# Power.net
KiCad netlist of a schematic drawn in Altium Designer
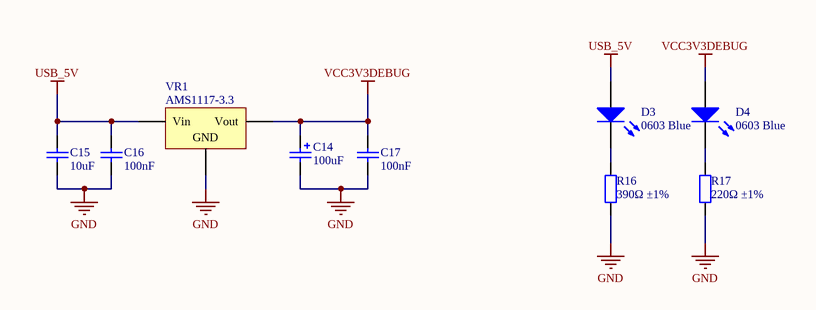
[diagram p0: Power.SchDoc]

(export (version "E")
  (design (tool "Eeschema 10.0.6"))
  (components
    (comp (ref "C14")
      (value "100uF")
      (footprint "CASE-B_3528")
      (description "Tantalum capacitor")
      (fields (field (name "MANUFACTURER") "AVX") (field (name "PARTNUMBER") "TAJB107K006RNJ"))
      (libsource (lib "Cap") (part "3528 100uF (107) 10% 6.3V"))
    )
    (comp (ref "C15")
      (value "10uF")
      (footprint "1206_C")
      (description "Chip capacitors")
      (fields
        (field (name "MANUFACTURER") "Samsung Electro-Mechanics")
        (field (name "PARTNUMBER") "CL31A106KBHNNNE")
      )
      (libsource (lib "Cap") (part "1206 10uF (106) 10% 50V"))
    )
    (comp (ref "C16")
      (value "100nF")
      (footprint "0402_C")
      (description "Chip capacitors")
      (fields
        (field (name "MANUFACTURER") "Samsung Electro-Mechanics")
        (field (name "PARTNUMBER") "CL05B104KO5NNNC")
      )
      (libsource (lib "Miscellaneous Devices LC") (part "0402 100nF (104) 10% 16V"))
    )
    (comp (ref "C17")
      (value "100nF")
      (footprint "1206_C")
      (description "Chip capacitors")
      (fields
        (field (name "MANUFACTURER") "Samsung Electro-Mechanics")
        (field (name "PARTNUMBER") "CL31B104KBCNNNC")
      )
      (libsource (lib "Miscellaneous Devices LC") (part "1206 100nF (104) 10% 50V"))
    )
    (comp (ref "D3")
      (value "0603 Blue")
      (footprint "0603_LED_S1")
      (description "LED")
      (libsource (lib "Miscellaneous Devices LC") (part "0603 LED Blue"))
    )
    (comp (ref "D4")
      (value "0603 Blue")
      (footprint "0603_LED_S1")
      (description "LED")
      (libsource (lib "Miscellaneous Devices LC") (part "0603 LED Blue"))
    )
    (comp (ref "R16")
      (value "390Ω ±1%")
      (footprint "0603_R")
      (description "Chip resistor")
      (fields (field (name "MANUFACTURER") "Uniroyal Elec") (field (name "PARTNUMBER") "0603WAF3900T5E"))
      (libsource (lib "RES") (part "0603 390R (3900) 1%"))
    )
    (comp (ref "R17")
      (value "220Ω ±1%")
      (footprint "0402_R")
      (description "Chip resistor")
      (fields (field (name "MANUFACTURER") "Uniroyal Elec") (field (name "PARTNUMBER") "0402WGF2200TCE"))
      (libsource (lib "RES") (part "0402 220R (2200) 1%"))
    )
    (comp (ref "VR1")
      (value "AMS1117-3.3")
      (footprint "SOT-223")
      (description "低压差线性稳压(LDO)")
      (libsource (lib "Miscellaneous Devices LC") (part "SOT-223 AMS1117-3.3"))
    )
  )
  (nets
    (net (code "1") (name "GND") (class "Default")
      (node (ref "C14") (pin "2") (pinfunction "2_2") (pintype "passive"))
      (node (ref "C15") (pin "1") (pinfunction "1_1") (pintype "passive"))
      (node (ref "C16") (pin "1") (pinfunction "1_1") (pintype "passive"))
      (node (ref "C17") (pin "1") (pinfunction "1_1") (pintype "passive"))
      (node (ref "R16") (pin "1") (pinfunction "1_1") (pintype "passive"))
      (node (ref "R17") (pin "1") (pinfunction "1_1") (pintype "passive"))
      (node (ref "VR1") (pin "1") (pinfunction "GND_1") (pintype "passive"))
    )
    (net (code "2") (name "Net-(D3-PadK)") (class "Default")
      (node (ref "D3") (pin "K") (pinfunction "K_K") (pintype "passive"))
      (node (ref "R16") (pin "2") (pinfunction "2_2") (pintype "passive"))
    )
    (net (code "3") (name "Net-(D4-PadK)") (class "Default")
      (node (ref "D4") (pin "K") (pinfunction "K_K") (pintype "passive"))
      (node (ref "R17") (pin "2") (pinfunction "2_2") (pintype "passive"))
    )
    (net (code "4") (name "USB_5V") (class "Default")
      (node (ref "C15") (pin "2") (pinfunction "2_2") (pintype "passive"))
      (node (ref "C16") (pin "2") (pinfunction "2_2") (pintype "passive"))
      (node (ref "D3") (pin "A") (pinfunction "A_A") (pintype "passive"))
      (node (ref "VR1") (pin "3") (pinfunction "Vin_3") (pintype "passive"))
    )
    (net (code "5") (name "VCC3V3DEBUG") (class "Default")
      (node (ref "C14") (pin "1") (pinfunction "1_1") (pintype "passive"))
      (node (ref "C17") (pin "2") (pinfunction "2_2") (pintype "passive"))
      (node (ref "D4") (pin "A") (pinfunction "A_A") (pintype "passive"))
      (node (ref "VR1") (pin "2") (pinfunction "Vout_2") (pintype "passive"))
    )
  )
)
